# LCmeter0-LCD-8pinlcd-PIC18F2550-COMP.net
KiCad netlist of a schematic drawn in EAGLE
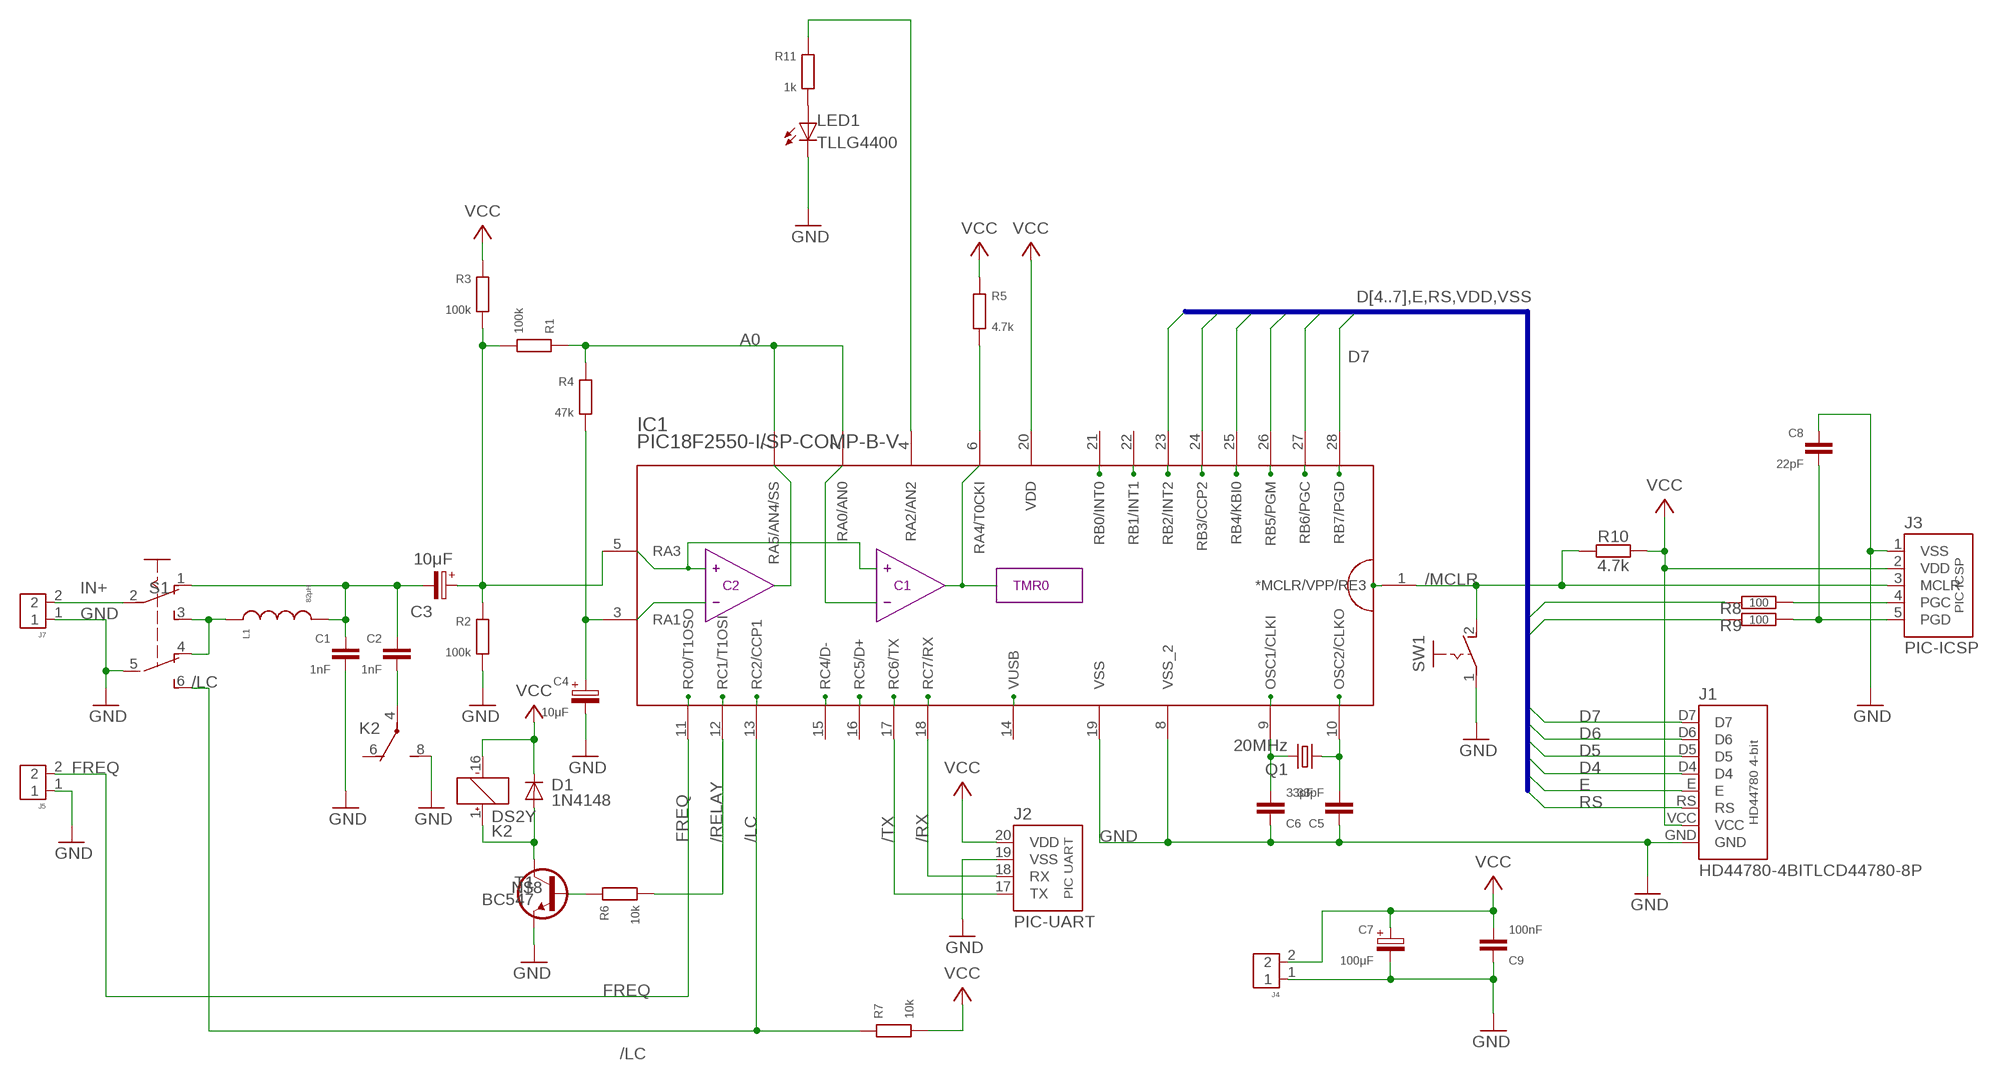
[diagram p0: schematic, sheet 1]

(export (version "E")
  (design (tool "Eeschema 10.0.6"))
  (components
    (comp (ref "C1")
      (value "1nF")
      (footprint "eagle-import:C050-025X060")
      (libsource (lib "eagle-import") (part "C025-025X060"))
    )
    (comp (ref "C2")
      (value "1nF")
      (footprint "eagle-import:C050-025X060")
      (libsource (lib "eagle-import") (part "C025-025X060"))
    )
    (comp (ref "C3")
      (value "10μF")
      (footprint "eagle-import:E2,5-4")
      (libsource (lib "eagle-import") (part "CPOLE2,5-4"))
    )
    (comp (ref "C4")
      (value "10μF")
      (footprint "eagle-import:E2,5-4")
      (libsource (lib "eagle-import") (part "CPOLE2,5-4"))
    )
    (comp (ref "C5")
      (value "33pF")
      (footprint "eagle-import:C025-020X036")
      (libsource (lib "eagle-import") (part "C025-020X036"))
    )
    (comp (ref "C6")
      (value "33pF")
      (footprint "eagle-import:C025-020X036")
      (libsource (lib "eagle-import") (part "C025-020X036"))
    )
    (comp (ref "C7")
      (value "100μF")
      (footprint "eagle-import:E2,5-5")
      (libsource (lib "eagle-import") (part "CPOLE2.5-5"))
    )
    (comp (ref "C8")
      (value "22pF")
      (footprint "eagle-import:C050-020X036")
      (libsource (lib "eagle-import") (part "C050-020X036"))
    )
    (comp (ref "C9")
      (value "100nF")
      (footprint "eagle-import:C025-020X036_V")
      (libsource (lib "eagle-import") (part "C025-020X036/V"))
    )
    (comp (ref "D1")
      (value "1N4148")
      (footprint "eagle-import:DO34-7")
      (libsource (lib "eagle-import") (part "1N414834-7"))
    )
    (comp (ref "IC1")
      (value "PIC18F2550-I/SP-COMP-B-V")
      (footprint "eagle-import:DIL28-3_V")
      (libsource (lib "eagle-import") (part "PIC18F2550-I/SP-COMP-B-V"))
    )
    (comp (ref "J1")
      (value "HD44780-4BITLCD44780-8P")
      (footprint "eagle-import:CONN-LCD44780")
      (libsource (lib "eagle-import") (part "HD44780-4BITLCD44780-8P"))
    )
    (comp (ref "J2")
      (value "PIC-UART")
      (footprint "eagle-import:PIC-UART")
      (libsource (lib "eagle-import") (part "PIC-UART"))
    )
    (comp (ref "J3")
      (value "PIC-ICSP")
      (footprint "eagle-import:PIC-ICSP")
      (libsource (lib "eagle-import") (part "PIC-ICSPICSP"))
    )
    (comp (ref "J4")
      (value "J4")
      (footprint "eagle-import:CONN-2P")
      (libsource (lib "eagle-import") (part "CONN-2P2P/H"))
    )
    (comp (ref "J5")
      (value "CONN-2P2P/V")
      (footprint "eagle-import:CONN-2P-V")
      (libsource (lib "eagle-import") (part "CONN-2P2P/V"))
    )
    (comp (ref "J7")
      (value "CONN-2P2P/V")
      (footprint "eagle-import:CONN-2P-V")
      (libsource (lib "eagle-import") (part "CONN-2P2P/V"))
    )
    (comp (ref "K2")
      (value "DS2Y")
      (footprint "eagle-import:DS2Y")
      (fields (field (name "MPN") "DS2Y-S-DC5V"))
      (libsource (lib "eagle-import") (part "DS2Y-S-DC5V"))
    )
    (comp (ref "L1")
      (value "82μH")
      (footprint "eagle-import:0207_10")
      (libsource (lib "eagle-import") (part "LAXIAL"))
    )
    (comp (ref "LED1")
      (value "TLLG4400")
      (footprint "eagle-import:LED3MM")
      (fields (field (name "MF") "VISHAY SEMICONDUCTOR"))
      (libsource (lib "eagle-import") (part "TLLG4400"))
    )
    (comp (ref "Q1")
      (value "20MHz")
      (footprint "eagle-import:HC49")
      (libsource (lib "eagle-import") (part "CRYSTALHC49"))
    )
    (comp (ref "R1")
      (value "100k")
      (footprint "eagle-import:0202_7")
      (libsource (lib "eagle-import") (part "R0202/7"))
    )
    (comp (ref "R2")
      (value "100k")
      (footprint "eagle-import:0202_7")
      (libsource (lib "eagle-import") (part "R0202/7"))
    )
    (comp (ref "R3")
      (value "100k")
      (footprint "eagle-import:0202_7")
      (libsource (lib "eagle-import") (part "R0202/7"))
    )
    (comp (ref "R4")
      (value "47k")
      (footprint "eagle-import:0202_7")
      (libsource (lib "eagle-import") (part "R0202/7"))
    )
    (comp (ref "R5")
      (value "4.7k")
      (footprint "eagle-import:0202_7")
      (libsource (lib "eagle-import") (part "R0202/7"))
    )
    (comp (ref "R6")
      (value "10k")
      (footprint "eagle-import:0202_7-V")
      (libsource (lib "eagle-import") (part "R0202/7-V"))
    )
    (comp (ref "R7")
      (value "10k")
      (footprint "eagle-import:0202_10-V")
      (libsource (lib "eagle-import") (part "R0202/10-V"))
    )
    (comp (ref "R8")
      (value "100")
      (footprint "eagle-import:0202_7-V")
      (libsource (lib "eagle-import") (part "R0202/7-V"))
    )
    (comp (ref "R9")
      (value "100")
      (footprint "eagle-import:0202_5-V")
      (libsource (lib "eagle-import") (part "R0202/5-V"))
    )
    (comp (ref "R10")
      (value "4.7k")
      (footprint "eagle-import:0202_7")
      (libsource (lib "eagle-import") (part "R0202/7"))
    )
    (comp (ref "R11")
      (value "1k")
      (footprint "eagle-import:0202_5-V")
      (libsource (lib "eagle-import") (part "R0202/5-V"))
    )
    (comp (ref "S1")
      (value "SL-SW-2P-2T")
      (footprint "eagle-import:SLSW-2P2T")
      (libsource (lib "eagle-import") (part "SL-SW-2P-2T"))
    )
    (comp (ref "SW1")
      (value "PB-1P-1T")
      (footprint "eagle-import:PB-1P1T")
      (libsource (lib "eagle-import") (part "PB-1P-1T"))
    )
    (comp (ref "T1")
      (value "BC547")
      (footprint "eagle-import:TO92-CBE-A")
      (libsource (lib "eagle-import") (part "BC547CBE-A"))
    )
  )
  (nets
    (net (code "3") (name "/A0") (class "Default")
      (node (ref "IC1") (pin "2") (pinfunction "RA0/AN0_2") (pintype "passive"))
      (node (ref "IC1") (pin "7") (pinfunction "RA5/AN4/SS_7") (pintype "passive"))
      (node (ref "R1") (pin "2") (pinfunction "2_2") (pintype "passive"))
      (node (ref "R4") (pin "2") (pinfunction "2_2") (pintype "passive"))
    )
    (net (code "4") (name "/D4") (class "Default")
      (node (ref "IC1") (pin "25") (pinfunction "RB4/KBI0_25") (pintype "passive"))
      (node (ref "J1") (pin "D4") (pinfunction "D4_D4") (pintype "passive"))
    )
    (net (code "5") (name "/D5") (class "Default")
      (node (ref "IC1") (pin "26") (pinfunction "RB5/PGM_26") (pintype "passive"))
      (node (ref "J1") (pin "D5") (pinfunction "D5_D5") (pintype "passive"))
    )
    (net (code "6") (name "/D6") (class "Default")
      (node (ref "IC1") (pin "27") (pinfunction "RB6/PGC_27") (pintype "passive"))
      (node (ref "J1") (pin "D6") (pinfunction "D6_D6") (pintype "passive"))
      (node (ref "R8") (pin "2") (pinfunction "2_2") (pintype "passive"))
    )
    (net (code "7") (name "/D7") (class "Default")
      (node (ref "IC1") (pin "28") (pinfunction "RB7/PGD_28") (pintype "passive"))
      (node (ref "J1") (pin "D7") (pinfunction "D7_D7") (pintype "passive"))
      (node (ref "R9") (pin "2") (pinfunction "2_2") (pintype "passive"))
    )
    (net (code "8") (name "/E") (class "Default")
      (node (ref "IC1") (pin "24") (pinfunction "RB3/CCP2_24") (pintype "passive"))
      (node (ref "J1") (pin "E") (pinfunction "E_E") (pintype "passive"))
    )
    (net (code "9") (name "/FREQ") (class "Default")
      (node (ref "IC1") (pin "11") (pinfunction "RC0/T1OSO_11") (pintype "passive"))
      (node (ref "J5") (pin "2") (pinfunction "2_2") (pintype "bidirectional"))
    )
    (net (code "10") (name "/IN+") (class "Default")
      (node (ref "J7") (pin "2") (pinfunction "2_2") (pintype "bidirectional"))
      (node (ref "S1") (pin "2") (pinfunction "P_2") (pintype "passive"))
    )
    (net (code "11") (name "/N$8") (class "Default")
      (node (ref "D1") (pin "A") (pinfunction "A_A") (pintype "passive"))
      (node (ref "K2") (pin "1") (pinfunction "+_1") (pintype "passive"))
      (node (ref "T1") (pin "C") (pinfunction "C_C") (pintype "passive"))
    )
    (net (code "12") (name "/RS") (class "Default")
      (node (ref "IC1") (pin "23") (pinfunction "RB2/INT2_23") (pintype "passive"))
      (node (ref "J1") (pin "RS") (pinfunction "RS_RS") (pintype "passive"))
    )
    (net (code "14") (name "/{slash}LC") (class "Default")
      (node (ref "IC1") (pin "13") (pinfunction "RC2/CCP1_13") (pintype "passive"))
      (node (ref "R7") (pin "2") (pinfunction "2_2") (pintype "passive"))
      (node (ref "S1") (pin "6") (pinfunction "S1_6") (pintype "passive"))
    )
    (net (code "15") (name "/{slash}MCLR") (class "Default")
      (node (ref "IC1") (pin "1") (pinfunction "*MCLR/VPP/RE3_1") (pintype "passive"))
      (node (ref "J3") (pin "3") (pinfunction "MCLR_3") (pintype "passive"))
      (node (ref "R10") (pin "2") (pinfunction "2_2") (pintype "passive"))
      (node (ref "SW1") (pin "2") (pinfunction "S_2") (pintype "passive"))
    )
    (net (code "16") (name "/{slash}RELAY") (class "Default")
      (node (ref "IC1") (pin "12") (pinfunction "RC1/T1OSI_12") (pintype "passive"))
      (node (ref "R6") (pin "1") (pinfunction "1_1") (pintype "passive"))
    )
    (net (code "17") (name "/{slash}RX") (class "Default")
      (node (ref "IC1") (pin "18") (pinfunction "RC7/RX_18") (pintype "passive"))
      (node (ref "J2") (pin "18") (pinfunction "RX_18") (pintype "passive"))
    )
    (net (code "18") (name "/{slash}TX") (class "Default")
      (node (ref "IC1") (pin "17") (pinfunction "RC6/TX_17") (pintype "passive"))
      (node (ref "J2") (pin "17") (pinfunction "TX_17") (pintype "passive"))
    )
    (net (code "19") (name "GND") (class "Default")
      (node (ref "C1") (pin "2") (pinfunction "2_2") (pintype "passive"))
      (node (ref "C4") (pin "-") (pinfunction "-_-") (pintype "passive"))
      (node (ref "C5") (pin "1") (pinfunction "1_1") (pintype "passive"))
      (node (ref "C6") (pin "1") (pinfunction "1_1") (pintype "passive"))
      (node (ref "C7") (pin "-") (pinfunction "-_-") (pintype "passive"))
      (node (ref "C8") (pin "1") (pinfunction "1_1") (pintype "passive"))
      (node (ref "C9") (pin "1") (pinfunction "1_1") (pintype "passive"))
      (node (ref "IC1") (pin "19") (pinfunction "VSS_19") (pintype "passive"))
      (node (ref "IC1") (pin "8") (pinfunction "VSS_2_8") (pintype "passive"))
      (node (ref "J1") (pin "GND") (pinfunction "GND_GND") (pintype "passive"))
      (node (ref "J2") (pin "19") (pinfunction "VSS_19") (pintype "passive"))
      (node (ref "J3") (pin "1") (pinfunction "VSS_1") (pintype "passive"))
      (node (ref "J4") (pin "1") (pinfunction "1_1") (pintype "bidirectional"))
      (node (ref "J5") (pin "1") (pinfunction "1_1") (pintype "bidirectional"))
      (node (ref "J7") (pin "1") (pinfunction "1_1") (pintype "bidirectional"))
      (node (ref "K2") (pin "8") (pinfunction "S_8") (pintype "passive"))
      (node (ref "LED1") (pin "K") (pinfunction "C_K") (pintype "passive"))
      (node (ref "R2") (pin "1") (pinfunction "1_1") (pintype "passive"))
      (node (ref "S1") (pin "5") (pinfunction "P1_5") (pintype "passive"))
      (node (ref "SW1") (pin "1") (pinfunction "P_1") (pintype "passive"))
      (node (ref "T1") (pin "E") (pinfunction "E_E") (pintype "passive"))
    )
    (net (code "20") (name "Net-(IC1-OSC1{slash}CLKI)") (class "Default")
      (node (ref "C6") (pin "2") (pinfunction "2_2") (pintype "passive"))
      (node (ref "IC1") (pin "9") (pinfunction "OSC1/CLKI_9") (pintype "passive"))
      (node (ref "Q1") (pin "2") (pinfunction "2_2") (pintype "passive"))
    )
    (net (code "21") (name "Net-(IC1-OSC2{slash}CLKO)") (class "Default")
      (node (ref "C5") (pin "2") (pinfunction "2_2") (pintype "passive"))
      (node (ref "IC1") (pin "10") (pinfunction "OSC2/CLKO_10") (pintype "passive"))
      (node (ref "Q1") (pin "1") (pinfunction "1_1") (pintype "passive"))
    )
    (net (code "22") (name "Net-(IC1-RA1)") (class "Default")
      (node (ref "C4") (pin "+") (pinfunction "+_+") (pintype "passive"))
      (node (ref "IC1") (pin "3") (pinfunction "RA1_3") (pintype "passive"))
      (node (ref "R4") (pin "1") (pinfunction "1_1") (pintype "passive"))
    )
    (net (code "23") (name "Net-(IC1-RA2{slash}AN2)") (class "Default")
      (node (ref "IC1") (pin "4") (pinfunction "RA2/AN2_4") (pintype "passive"))
      (node (ref "R11") (pin "2") (pinfunction "2_2") (pintype "passive"))
    )
    (net (code "24") (name "Net-(IC1-RA3)") (class "Default")
      (node (ref "C3") (pin "+") (pinfunction "+_+") (pintype "passive"))
      (node (ref "IC1") (pin "5") (pinfunction "RA3_5") (pintype "passive"))
      (node (ref "R1") (pin "1") (pinfunction "1_1") (pintype "passive"))
      (node (ref "R2") (pin "2") (pinfunction "2_2") (pintype "passive"))
      (node (ref "R3") (pin "1") (pinfunction "1_1") (pintype "passive"))
    )
    (net (code "25") (name "Net-(IC1-RA4{slash}T0CKI)") (class "Default")
      (node (ref "IC1") (pin "6") (pinfunction "RA4/T0CKI_6") (pintype "passive"))
      (node (ref "R5") (pin "1") (pinfunction "1_1") (pintype "passive"))
    )
    (net (code "26") (name "Net-(J3-PGC)") (class "Default")
      (node (ref "J3") (pin "4") (pinfunction "PGC_4") (pintype "passive"))
      (node (ref "R8") (pin "1") (pinfunction "1_1") (pintype "passive"))
    )
    (net (code "27") (name "Net-(J3-PGD)") (class "Default")
      (node (ref "C8") (pin "2") (pinfunction "2_2") (pintype "passive"))
      (node (ref "J3") (pin "5") (pinfunction "PGD_5") (pintype "passive"))
      (node (ref "R9") (pin "1") (pinfunction "1_1") (pintype "passive"))
    )
    (net (code "28") (name "Net-(K2B-P)") (class "Default")
      (node (ref "C2") (pin "2") (pinfunction "2_2") (pintype "passive"))
      (node (ref "K2") (pin "4") (pinfunction "P_4") (pintype "passive"))
    )
    (net (code "29") (name "Net-(LED1-PadA)") (class "Default")
      (node (ref "LED1") (pin "A") (pinfunction "A_A") (pintype "passive"))
      (node (ref "R11") (pin "1") (pinfunction "1_1") (pintype "passive"))
    )
    (net (code "30") (name "Net-(R6-Pad2)") (class "Default")
      (node (ref "R6") (pin "2") (pinfunction "2_2") (pintype "passive"))
      (node (ref "T1") (pin "B") (pinfunction "B_B") (pintype "passive"))
    )
    (net (code "31") (name "Net-(S1-O)") (class "Default")
      (node (ref "C1") (pin "1") (pinfunction "1_1") (pintype "passive"))
      (node (ref "C2") (pin "1") (pinfunction "1_1") (pintype "passive"))
      (node (ref "C3") (pin "-") (pinfunction "-_-") (pintype "passive"))
      (node (ref "L1") (pin "2") (pinfunction "2_2") (pintype "passive"))
      (node (ref "S1") (pin "1") (pinfunction "O_1") (pintype "passive"))
    )
    (net (code "32") (name "Net-(S1-O1)") (class "Default")
      (node (ref "L1") (pin "1") (pinfunction "1_1") (pintype "passive"))
      (node (ref "S1") (pin "3") (pinfunction "S_3") (pintype "passive"))
      (node (ref "S1") (pin "4") (pinfunction "O1_4") (pintype "passive"))
    )
    (net (code "33") (name "VCC") (class "Default")
      (node (ref "C7") (pin "+") (pinfunction "+_+") (pintype "passive"))
      (node (ref "C9") (pin "2") (pinfunction "2_2") (pintype "passive"))
      (node (ref "D1") (pin "C") (pinfunction "C_C") (pintype "passive"))
      (node (ref "IC1") (pin "20") (pinfunction "VDD_20") (pintype "passive"))
      (node (ref "J1") (pin "VCC") (pinfunction "VCC_VCC") (pintype "passive"))
      (node (ref "J2") (pin "20") (pinfunction "VDD_20") (pintype "passive"))
      (node (ref "J3") (pin "2") (pinfunction "VDD_2") (pintype "passive"))
      (node (ref "J4") (pin "2") (pinfunction "2_2") (pintype "bidirectional"))
      (node (ref "K2") (pin "16") (pinfunction "-_16") (pintype "passive"))
      (node (ref "R10") (pin "1") (pinfunction "1_1") (pintype "passive"))
      (node (ref "R3") (pin "2") (pinfunction "2_2") (pintype "passive"))
      (node (ref "R5") (pin "2") (pinfunction "2_2") (pintype "passive"))
      (node (ref "R7") (pin "1") (pinfunction "1_1") (pintype "passive"))
    )
    (net (code "34") (name "unconnected-(IC1-RB0{slash}INT0-Pad21)") (class "Default")
      (node (ref "IC1") (pin "21") (pinfunction "RB0/INT0_21") (pintype "passive"))
    )
    (net (code "35") (name "unconnected-(IC1-RB1{slash}INT1-Pad22)") (class "Default")
      (node (ref "IC1") (pin "22") (pinfunction "RB1/INT1_22") (pintype "passive"))
    )
    (net (code "36") (name "unconnected-(IC1-RC4{slash}D--Pad15)") (class "Default")
      (node (ref "IC1") (pin "15") (pinfunction "RC4/D-_15") (pintype "passive"))
    )
    (net (code "37") (name "unconnected-(IC1-RC5{slash}D+-Pad16)") (class "Default")
      (node (ref "IC1") (pin "16") (pinfunction "RC5/D+_16") (pintype "passive"))
    )
    (net (code "38") (name "unconnected-(IC1-VUSB-Pad14)") (class "Default")
      (node (ref "IC1") (pin "14") (pinfunction "VUSB_14") (pintype "passive"))
    )
    (net (code "39") (name "unconnected-(K2B-O-Pad6)") (class "Default")
      (node (ref "K2") (pin "6") (pinfunction "O_6") (pintype "passive"))
    )
  )
)
